# ST7735.net
KiCad netlist of a schematic drawn in Altium Designer
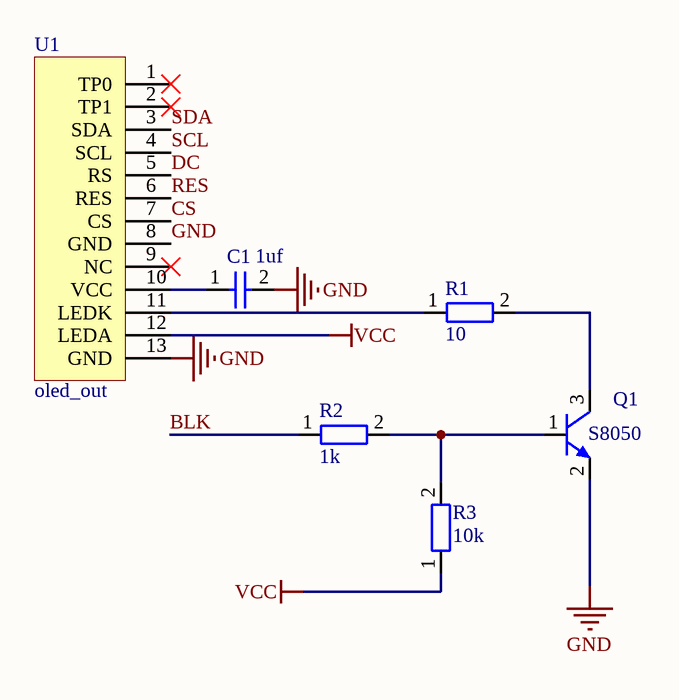
[diagram p0: ST7735.SchDoc]

(export (version "E")
  (design (tool "Eeschema 10.0.6"))
  (components
    (comp (ref "C1") (value "1uf") (footprint "CAP") (libsource (lib "ST7735") (part "CAP")))
    (comp (ref "Q1") (value "~") (footprint "S8050") (libsource (lib "ST7735") (part "S8050")))
    (comp (ref "R1") (value "10") (footprint "RES") (libsource (lib "") (part "RES_1")))
    (comp (ref "R2") (value "1k") (footprint "RES") (libsource (lib "ST7735") (part "RES")))
    (comp (ref "R3") (value "10k") (footprint "RES") (libsource (lib "ST7735") (part "RES")))
    (comp (ref "U1") (value "oled_out") (footprint "oled_out") (libsource (lib "ST7735") (part "oled_out")))
  )
  (nets
    (net (code "1") (name "/BLK") (class "Default")
      (node (ref "R2") (pin "1") (pinfunction "1_1") (pintype "passive"))
    )
    (net (code "2") (name "/CS") (class "Default")
      (node (ref "U1") (pin "7") (pinfunction "CS_7") (pintype "passive"))
    )
    (net (code "3") (name "/DC") (class "Default")
      (node (ref "U1") (pin "5") (pinfunction "RS_5") (pintype "passive"))
    )
    (net (code "4") (name "/RES") (class "Default")
      (node (ref "U1") (pin "6") (pinfunction "RES_6") (pintype "passive"))
    )
    (net (code "5") (name "/SCL") (class "Default")
      (node (ref "U1") (pin "4") (pinfunction "SCL_4") (pintype "passive"))
    )
    (net (code "6") (name "/SDA") (class "Default")
      (node (ref "U1") (pin "3") (pinfunction "SDA_3") (pintype "passive"))
    )
    (net (code "7") (name "GND") (class "Default")
      (node (ref "C1") (pin "2") (pinfunction "2_2") (pintype "passive"))
      (node (ref "Q1") (pin "2") (pinfunction "2_2") (pintype "passive"))
      (node (ref "U1") (pin "13") (pinfunction "GND_13") (pintype "passive"))
      (node (ref "U1") (pin "8") (pinfunction "GND_8") (pintype "passive"))
    )
    (net (code "8") (name "Net-(Q1-Pad1)") (class "Default")
      (node (ref "Q1") (pin "1") (pinfunction "1_1") (pintype "passive"))
      (node (ref "R2") (pin "2") (pinfunction "2_2") (pintype "passive"))
      (node (ref "R3") (pin "2") (pinfunction "2_2") (pintype "passive"))
    )
    (net (code "9") (name "Net-(Q1-Pad3)") (class "Default")
      (node (ref "Q1") (pin "3") (pinfunction "3_3") (pintype "passive"))
      (node (ref "R1") (pin "2") (pinfunction "2_2") (pintype "passive"))
    )
    (net (code "10") (name "Net-(U1-LEDK)") (class "Default")
      (node (ref "R1") (pin "1") (pinfunction "1_1") (pintype "passive"))
      (node (ref "U1") (pin "11") (pinfunction "LEDK_11") (pintype "passive"))
    )
    (net (code "11") (name "Net-(U1-VCC)") (class "Default")
      (node (ref "C1") (pin "1") (pinfunction "1_1") (pintype "passive"))
      (node (ref "U1") (pin "10") (pinfunction "VCC_10") (pintype "passive"))
    )
    (net (code "12") (name "VCC") (class "Default")
      (node (ref "R3") (pin "1") (pinfunction "1_1") (pintype "passive"))
      (node (ref "U1") (pin "12") (pinfunction "LEDA_12") (pintype "passive"))
    )
    (net (code "13") (name "unconnected-(U1-NC-Pad9)") (class "Default")
      (node (ref "U1") (pin "9") (pinfunction "NC_9") (pintype "passive+no_connect"))
    )
    (net (code "14") (name "unconnected-(U1-TP0-Pad1)") (class "Default")
      (node (ref "U1") (pin "1") (pinfunction "TP0_1") (pintype "passive+no_connect"))
    )
    (net (code "15") (name "unconnected-(U1-TP1-Pad2)") (class "Default")
      (node (ref "U1") (pin "2") (pinfunction "TP1_2") (pintype "passive+no_connect"))
    )
  )
)
